# ws2812b-Breakout.net
KiCad netlist of a schematic drawn in EAGLE
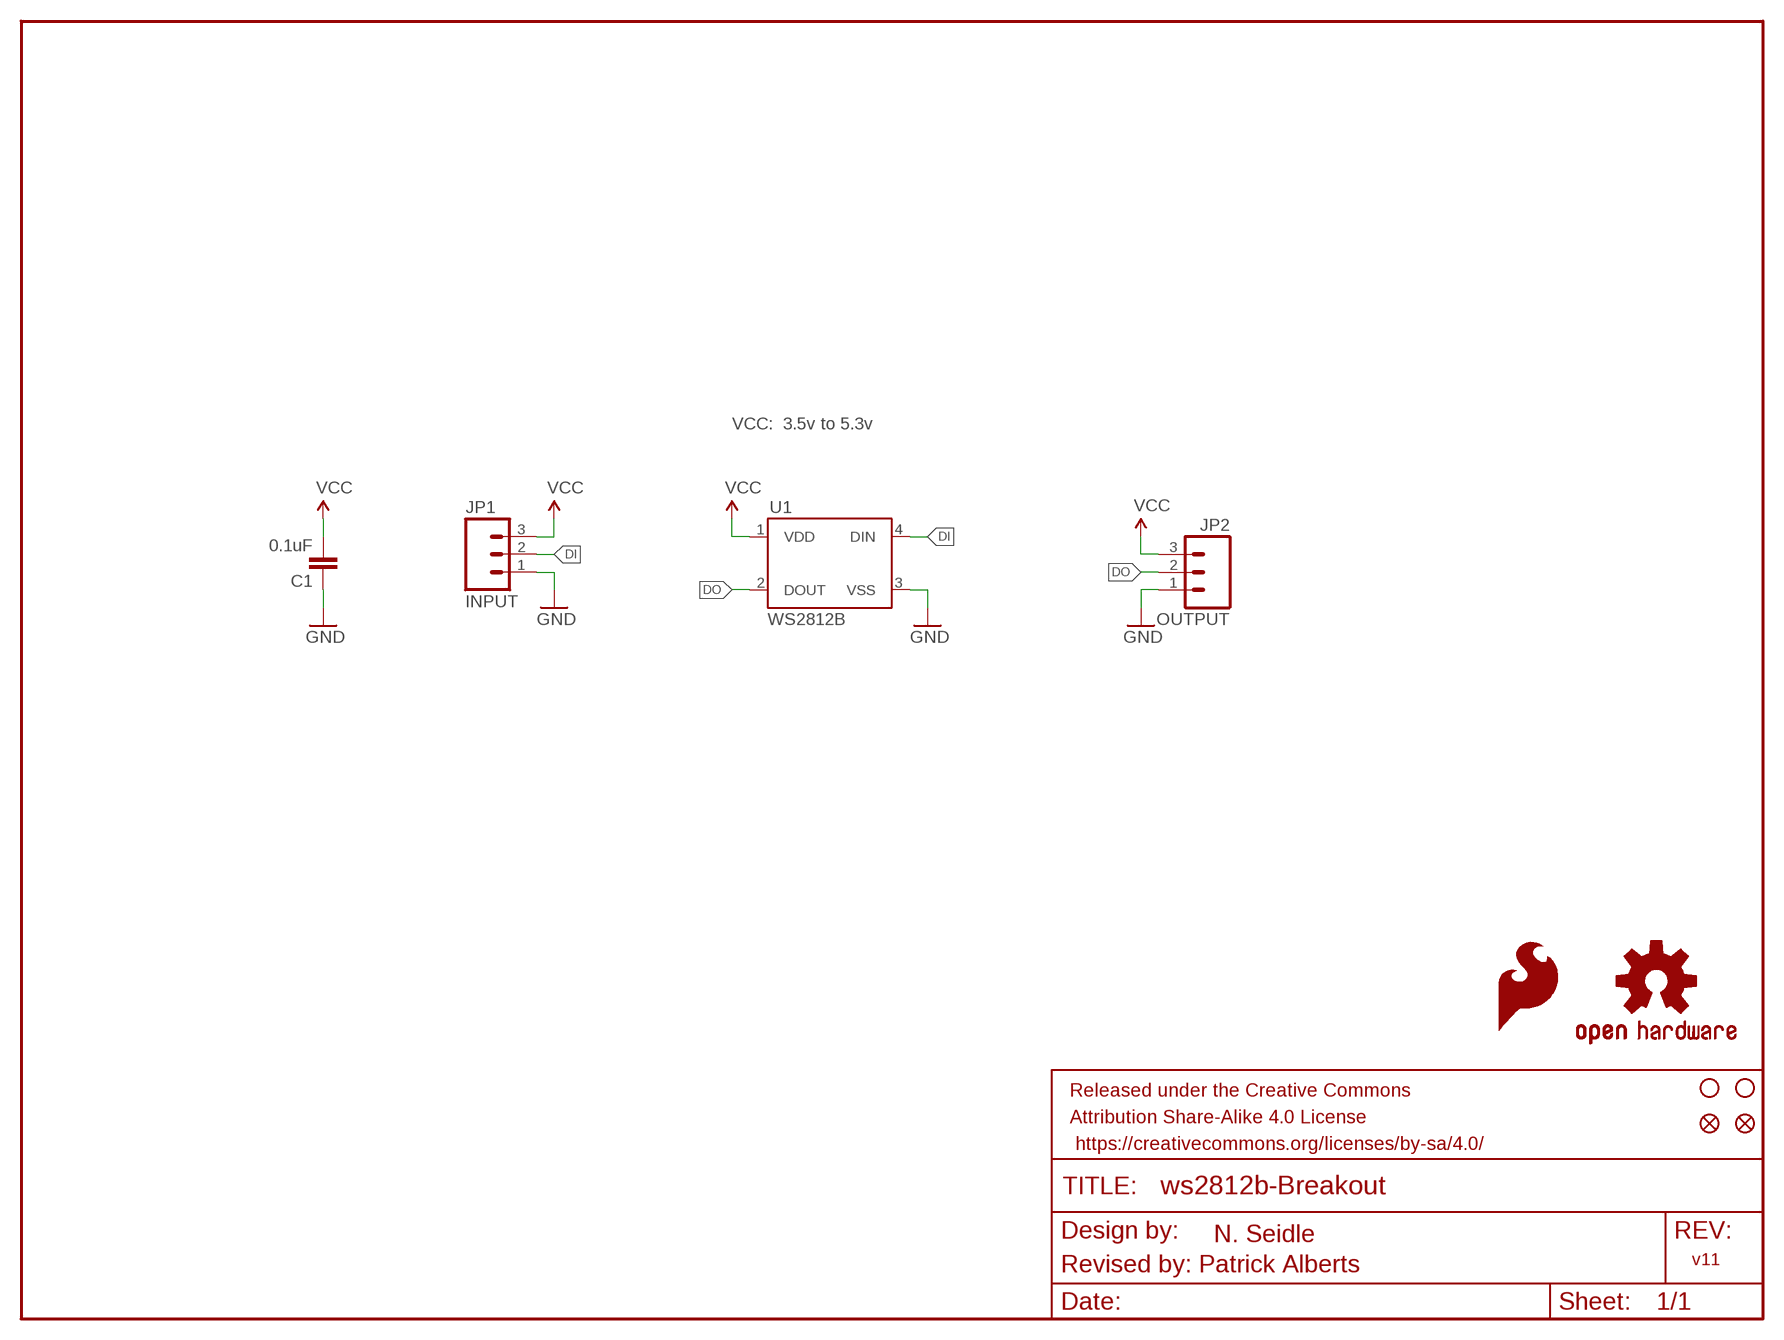
[diagram p0: schematic, sheet 1]

(export (version "E")
  (design (tool "Eeschema 10.0.6"))
  (components
    (comp (ref "C1")
      (value "0.1uF")
      (footprint "eagle-import:0603-CAP")
      (libsource (lib "eagle-import") (part "0.1UF-25V(+80/-20%)(0603)"))
    )
    (comp (ref "FID1")
      (value "FIDUCIALUFIDUCIAL")
      (footprint "eagle-import:MICRO-FIDUCIAL")
      (libsource (lib "eagle-import") (part "FIDUCIALUFIDUCIAL"))
    )
    (comp (ref "FID2")
      (value "FIDUCIALUFIDUCIAL")
      (footprint "eagle-import:MICRO-FIDUCIAL")
      (libsource (lib "eagle-import") (part "FIDUCIALUFIDUCIAL"))
    )
    (comp (ref "FRAME1")
      (value "FRAME-LETTER")
      (footprint "eagle-import:CREATIVE_COMMONS")
      (fields (field (name "DESIGNER") "NAME"))
      (libsource (lib "eagle-import") (part "FRAME-LETTER"))
    )
    (comp (ref "JP1")
      (value "INPUT")
      (footprint "eagle-import:1X03")
      (libsource (lib "eagle-import") (part "M03PTH"))
    )
    (comp (ref "JP2")
      (value "OUTPUT")
      (footprint "eagle-import:1X03")
      (libsource (lib "eagle-import") (part "M03PTH"))
    )
    (comp (ref "JP4")
      (value "STAND-OFF")
      (footprint "eagle-import:STAND-OFF")
      (libsource (lib "eagle-import") (part "STAND-OFF"))
    )
    (comp (ref "JP15")
      (value "STAND-OFF")
      (footprint "eagle-import:STAND-OFF")
      (libsource (lib "eagle-import") (part "STAND-OFF"))
    )
    (comp (ref "LOGO1")
      (value "OSHW-LOGOS")
      (footprint "eagle-import:OSHW-LOGO-S")
      (libsource (lib "eagle-import") (part "OSHW-LOGOS"))
    )
    (comp (ref "LOGO2")
      (value "SFE_LOGO_FLAME.1_INCH")
      (footprint "eagle-import:SFE_LOGO_FLAME_.1")
      (libsource (lib "eagle-import") (part "SFE_LOGO_FLAME.1_INCH"))
    )
    (comp (ref "U1")
      (value "WS2812B")
      (footprint "eagle-import:WS2812B")
      (libsource (lib "eagle-import") (part "WS2812B"))
    )
  )
  (nets
    (net (code "1") (name "DI") (class "Default")
      (node (ref "JP1") (pin "2") (pinfunction "2_2") (pintype "passive"))
      (node (ref "U1") (pin "4") (pinfunction "DIN_4") (pintype "input"))
    )
    (net (code "2") (name "DO") (class "Default")
      (node (ref "JP2") (pin "2") (pinfunction "2_2") (pintype "passive"))
      (node (ref "U1") (pin "2") (pinfunction "DOUT_2") (pintype "output"))
    )
    (net (code "3") (name "GND") (class "Default")
      (node (ref "C1") (pin "1") (pinfunction "1_1") (pintype "passive"))
      (node (ref "JP1") (pin "1") (pinfunction "1_1") (pintype "passive"))
      (node (ref "JP2") (pin "1") (pinfunction "1_1") (pintype "passive"))
      (node (ref "U1") (pin "3") (pinfunction "VSS_3") (pintype "power_in"))
    )
    (net (code "4") (name "VCC") (class "Default")
      (node (ref "C1") (pin "2") (pinfunction "2_2") (pintype "passive"))
      (node (ref "JP1") (pin "3") (pinfunction "3_3") (pintype "passive"))
      (node (ref "JP2") (pin "3") (pinfunction "3_3") (pintype "passive"))
      (node (ref "U1") (pin "1") (pinfunction "VDD_1") (pintype "power_in"))
    )
  )
)
